# Sheet1.net
KiCad netlist of a schematic drawn in Altium Designer
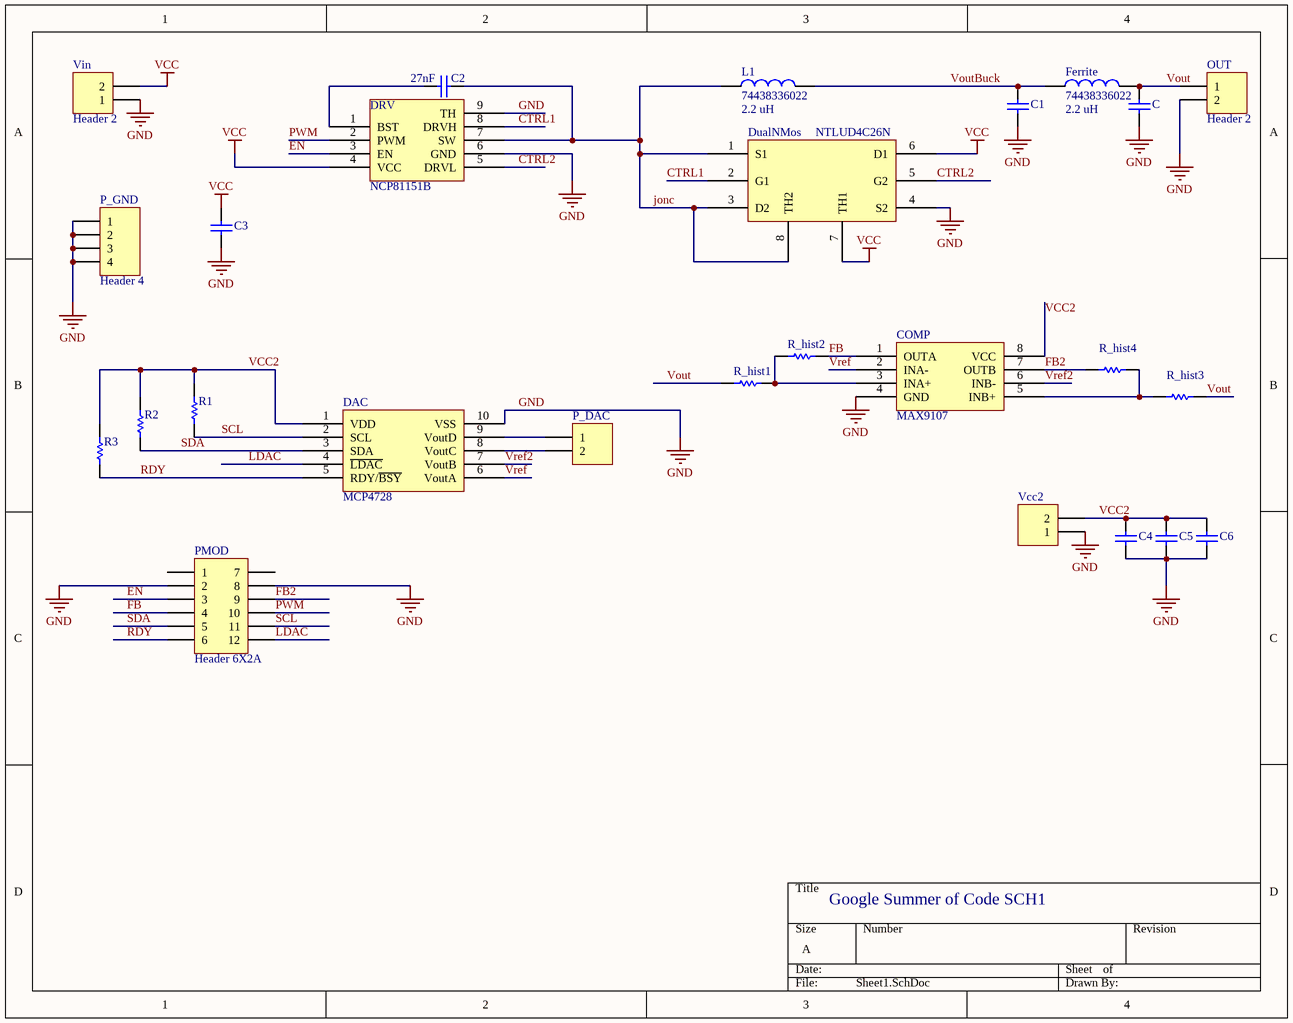
[diagram p0: Sheet1.SchDoc]

(export (version "E")
  (design (tool "Eeschema 10.0.6"))
  (components
    (comp (ref "C")
      (value "Cap")
      (footprint "Miscellaneous Devices:0603")
      (description "Capacitor")
      (fields (field (name "PUBLISHER") "Altium Limited"))
      (libsource (lib "Miscellaneous Devices") (part "Cap"))
    )
    (comp (ref "C1")
      (value "Cap")
      (footprint "Miscellaneous Devices:C1210_M")
      (description "Capacitor")
      (fields (field (name "PUBLISHER") "Altium Limited"))
      (libsource (lib "Miscellaneous Devices") (part "Cap"))
    )
    (comp (ref "C2")
      (value "27nF")
      (footprint "C0805")
      (description "Capacitor")
      (fields (field (name "Comment") "Cap") (field (name "PUBLISHER") "Altium Limited"))
      (libsource (lib "Miscellaneous Devices") (part "Cap"))
    )
    (comp (ref "C3")
      (value "Cap")
      (footprint "Miscellaneous Devices:C1210_M")
      (description "Capacitor")
      (fields (field (name "PUBLISHER") "Altium Limited"))
      (libsource (lib "Miscellaneous Devices") (part "Cap"))
    )
    (comp (ref "C4")
      (value "Cap")
      (footprint "Miscellaneous Devices:0402")
      (description "Capacitor")
      (fields (field (name "PUBLISHER") "Altium Limited"))
      (libsource (lib "Miscellaneous Devices") (part "Cap"))
    )
    (comp (ref "C5")
      (value "Cap")
      (footprint "Miscellaneous Devices:0402")
      (description "Capacitor")
      (fields (field (name "PUBLISHER") "Altium Limited"))
      (libsource (lib "Miscellaneous Devices") (part "Cap"))
    )
    (comp (ref "C6")
      (value "Cap")
      (footprint "Miscellaneous Devices:0402")
      (description "Capacitor")
      (fields (field (name "PUBLISHER") "Altium Limited"))
      (libsource (lib "Miscellaneous Devices") (part "Cap"))
    )
    (comp (ref "COMP") (value "MAX9107") (footprint "SOT23-8") (libsource (lib "BuckLib") (part "MAX9107")))
    (comp (ref "DAC")
      (value "MCP4728")
      (footprint "TSSOP50P500X110-10N")
      (libsource (lib "BuckLib") (part "MCP4728"))
    )
    (comp (ref "DRV")
      (value "NCP81151B")
      (footprint "QFN50P200X200X80_HS-9N")
      (libsource (lib "BuckLib") (part "NCP81151B"))
    )
    (comp (ref "DualNMos") (value "NTLUD4C26N") (libsource (lib "BuckLib") (part "NTLUD4C26N")))
    (comp (ref "Ferrite")
      (value "74438336022")
      (footprint "0402-A")
      (description "WE-MAPI SMD Shielded Power Inductor, size 3020, 2.2 uH")
      (fields (field (name "ALTIUM_VALUE") "2.2 uH") (field (name "PUBLISHER") "Wurth Elektronik"))
      (libsource (lib "ALTIUM-WE-MAPI-rev16b") (part "74438336022"))
    )
    (comp (ref "L1")
      (value "74438336022")
      (footprint "WE-MAPI_3020")
      (description "WE-MAPI SMD Shielded Power Inductor, size 3020, 2.2 uH")
      (fields (field (name "ALTIUM_VALUE") "2.2 uH") (field (name "PUBLISHER") "Wurth Elektronik"))
      (libsource (lib "ALTIUM-WE-MAPI-rev16b") (part "74438336022"))
    )
    (comp (ref "OUT")
      (value "Header 2")
      (footprint "HDR1X2")
      (description "Header, 2-Pin")
      (fields (field (name "PUBLISHER") "Altium Limited"))
      (libsource (lib "Miscellaneous Connectors") (part "Header 2"))
    )
    (comp (ref "PMOD")
      (value "Header 6X2A")
      (footprint "HDR2X6_CEN")
      (description "Header, 6-Pin, Dual row")
      (fields (field (name "PUBLISHER") "Altium Limited"))
      (libsource (lib "Miscellaneous Connectors") (part "Header 6X2A"))
    )
    (comp (ref "P_DAC")
      (value "Header 2")
      (footprint "HDR1X2")
      (description "Header, 2-Pin")
      (fields (field (name "PUBLISHER") "Altium Limited"))
      (libsource (lib "Miscellaneous Connectors") (part "Header 2"))
    )
    (comp (ref "P_GND")
      (value "Header 4")
      (footprint "HDR1X4")
      (description "Header, 4-Pin")
      (fields (field (name "PUBLISHER") "Altium Limited"))
      (libsource (lib "Miscellaneous Connectors") (part "Header 4"))
    )
    (comp (ref "R1")
      (value "Res1")
      (footprint "C0805")
      (description "Resistor")
      (fields (field (name "PUBLISHER") "Altium Limited"))
      (libsource (lib "Miscellaneous Devices") (part "Res1"))
    )
    (comp (ref "R2")
      (value "Res1")
      (footprint "C0805")
      (description "Resistor")
      (fields (field (name "PUBLISHER") "Altium Limited"))
      (libsource (lib "Miscellaneous Devices") (part "Res1"))
    )
    (comp (ref "R3")
      (value "Res1")
      (footprint "C0805")
      (description "Resistor")
      (fields (field (name "PUBLISHER") "Altium Limited"))
      (libsource (lib "Miscellaneous Devices") (part "Res1"))
    )
    (comp (ref "R_hist1")
      (value "Res1")
      (footprint "C0805")
      (description "Resistor")
      (fields (field (name "PUBLISHER") "Altium Limited"))
      (libsource (lib "Miscellaneous Devices") (part "Res1"))
    )
    (comp (ref "R_hist2")
      (value "Res1")
      (footprint "C0805")
      (description "Resistor")
      (fields (field (name "PUBLISHER") "Altium Limited"))
      (libsource (lib "Miscellaneous Devices") (part "Res1"))
    )
    (comp (ref "R_hist3")
      (value "Res1")
      (footprint "C0805")
      (description "Resistor")
      (fields (field (name "PUBLISHER") "Altium Limited"))
      (libsource (lib "Miscellaneous Devices") (part "Res1"))
    )
    (comp (ref "R_hist4")
      (value "Res1")
      (footprint "C0805")
      (description "Resistor")
      (fields (field (name "PUBLISHER") "Altium Limited"))
      (libsource (lib "Miscellaneous Devices") (part "Res1"))
    )
    (comp (ref "Vcc2")
      (value "Header 2")
      (footprint "HDR1X2")
      (description "Header, 2-Pin")
      (fields (field (name "PUBLISHER") "Altium Limited"))
      (libsource (lib "") (part "Header 2_1"))
    )
    (comp (ref "Vin")
      (value "Header 2")
      (footprint "HDR1X2")
      (description "Header, 2-Pin")
      (fields (field (name "PUBLISHER") "Altium Limited"))
      (libsource (lib "") (part "Header 2_1"))
    )
  )
  (nets
    (net (code "1") (name "/CTRL1") (class "Default")
      (node (ref "DRV") (pin "8") (pinfunction "DRVH_8") (pintype "passive"))
      (node (ref "DualNMos") (pin "2") (pinfunction "G1_2") (pintype "passive"))
    )
    (net (code "2") (name "/CTRL2") (class "Default")
      (node (ref "DRV") (pin "5") (pinfunction "DRVL_5") (pintype "passive"))
      (node (ref "DualNMos") (pin "5") (pinfunction "G2_5") (pintype "passive"))
    )
    (net (code "3") (name "/EN") (class "Default")
      (node (ref "DRV") (pin "3") (pinfunction "EN_3") (pintype "passive"))
      (node (ref "PMOD") (pin "3") (pinfunction "3_3") (pintype "passive"))
    )
    (net (code "4") (name "/FB") (class "Default")
      (node (ref "COMP") (pin "1") (pinfunction "OUTA_1") (pintype "passive"))
      (node (ref "PMOD") (pin "4") (pinfunction "4_4") (pintype "passive"))
      (node (ref "R_hist2") (pin "1") (pinfunction "1_1") (pintype "passive"))
    )
    (net (code "5") (name "/FB2") (class "Default")
      (node (ref "COMP") (pin "7") (pinfunction "OUTB_7") (pintype "passive"))
      (node (ref "PMOD") (pin "9") (pinfunction "9_9") (pintype "passive"))
      (node (ref "R_hist4") (pin "2") (pinfunction "2_2") (pintype "passive"))
    )
    (net (code "6") (name "/LDAC") (class "Default")
      (node (ref "DAC") (pin "4") (pinfunction "~{LDAC}_4") (pintype "passive"))
      (node (ref "PMOD") (pin "12") (pinfunction "12_12") (pintype "passive"))
    )
    (net (code "7") (name "/PWM") (class "Default")
      (node (ref "DRV") (pin "2") (pinfunction "PWM_2") (pintype "passive"))
      (node (ref "PMOD") (pin "10") (pinfunction "10_10") (pintype "passive"))
    )
    (net (code "8") (name "/RDY") (class "Default")
      (node (ref "DAC") (pin "5") (pinfunction "RDY/~{BSY}_5") (pintype "passive"))
      (node (ref "PMOD") (pin "6") (pinfunction "6_6") (pintype "passive"))
      (node (ref "R3") (pin "1") (pinfunction "1_1") (pintype "passive"))
    )
    (net (code "9") (name "/SCL") (class "Default")
      (node (ref "DAC") (pin "2") (pinfunction "SCL_2") (pintype "passive"))
      (node (ref "PMOD") (pin "11") (pinfunction "11_11") (pintype "passive"))
      (node (ref "R1") (pin "1") (pinfunction "1_1") (pintype "passive"))
    )
    (net (code "10") (name "/SDA") (class "Default")
      (node (ref "DAC") (pin "3") (pinfunction "SDA_3") (pintype "passive"))
      (node (ref "PMOD") (pin "5") (pinfunction "5_5") (pintype "passive"))
      (node (ref "R2") (pin "1") (pinfunction "1_1") (pintype "passive"))
    )
    (net (code "11") (name "/VCC2") (class "Default")
      (node (ref "C4") (pin "1") (pinfunction "1_1") (pintype "passive"))
      (node (ref "C5") (pin "1") (pinfunction "1_1") (pintype "passive"))
      (node (ref "C6") (pin "1") (pinfunction "1_1") (pintype "passive"))
      (node (ref "COMP") (pin "8") (pinfunction "VCC_8") (pintype "passive"))
      (node (ref "DAC") (pin "1") (pinfunction "VDD_1") (pintype "passive"))
      (node (ref "R1") (pin "2") (pinfunction "2_2") (pintype "passive"))
      (node (ref "R2") (pin "2") (pinfunction "2_2") (pintype "passive"))
      (node (ref "R3") (pin "2") (pinfunction "2_2") (pintype "passive"))
      (node (ref "Vcc2") (pin "2") (pinfunction "2_2") (pintype "passive"))
    )
    (net (code "12") (name "/Vout") (class "Default")
      (node (ref "C") (pin "2") (pinfunction "2_2") (pintype "passive"))
      (node (ref "Ferrite") (pin "2") (pinfunction "2_2") (pintype "passive"))
      (node (ref "OUT") (pin "1") (pinfunction "1_1") (pintype "passive"))
      (node (ref "R_hist1") (pin "2") (pinfunction "2_2") (pintype "passive"))
      (node (ref "R_hist3") (pin "1") (pinfunction "1_1") (pintype "passive"))
    )
    (net (code "13") (name "/VoutBuck") (class "Default")
      (node (ref "C1") (pin "2") (pinfunction "2_2") (pintype "passive"))
      (node (ref "Ferrite") (pin "1") (pinfunction "1_1") (pintype "passive"))
      (node (ref "L1") (pin "2") (pinfunction "2_2") (pintype "passive"))
    )
    (net (code "14") (name "/Vref") (class "Default")
      (node (ref "COMP") (pin "2") (pinfunction "INA-_2") (pintype "passive"))
      (node (ref "DAC") (pin "6") (pinfunction "VoutA_6") (pintype "passive"))
    )
    (net (code "15") (name "/Vref2") (class "Default")
      (node (ref "COMP") (pin "6") (pinfunction "INB-_6") (pintype "passive"))
      (node (ref "DAC") (pin "7") (pinfunction "VoutB_7") (pintype "passive"))
    )
    (net (code "16") (name "/jonc") (class "Default")
      (node (ref "C2") (pin "1") (pinfunction "1_1") (pintype "passive"))
      (node (ref "DRV") (pin "7") (pinfunction "SW_7") (pintype "passive"))
      (node (ref "DualNMos") (pin "1") (pinfunction "S1_1") (pintype "passive"))
      (node (ref "DualNMos") (pin "3") (pinfunction "D2_3") (pintype "passive"))
      (node (ref "DualNMos") (pin "8") (pinfunction "TH2_8") (pintype "passive"))
      (node (ref "L1") (pin "1") (pinfunction "1_1") (pintype "passive"))
    )
    (net (code "17") (name "GND") (class "Default")
      (node (ref "C") (pin "1") (pinfunction "1_1") (pintype "passive"))
      (node (ref "C1") (pin "1") (pinfunction "1_1") (pintype "passive"))
      (node (ref "C3") (pin "2") (pinfunction "2_2") (pintype "passive"))
      (node (ref "C4") (pin "2") (pinfunction "2_2") (pintype "passive"))
      (node (ref "C5") (pin "2") (pinfunction "2_2") (pintype "passive"))
      (node (ref "C6") (pin "2") (pinfunction "2_2") (pintype "passive"))
      (node (ref "COMP") (pin "4") (pinfunction "GND_4") (pintype "passive"))
      (node (ref "DAC") (pin "10") (pinfunction "VSS_10") (pintype "passive"))
      (node (ref "DRV") (pin "6") (pinfunction "GND_6") (pintype "passive"))
      (node (ref "DRV") (pin "9") (pinfunction "TH_9") (pintype "passive"))
      (node (ref "DualNMos") (pin "4") (pinfunction "S2_4") (pintype "passive"))
      (node (ref "OUT") (pin "2") (pinfunction "2_2") (pintype "passive"))
      (node (ref "PMOD") (pin "2") (pinfunction "2_2") (pintype "passive"))
      (node (ref "PMOD") (pin "8") (pinfunction "8_8") (pintype "passive"))
      (node (ref "P_GND") (pin "1") (pinfunction "1_1") (pintype "passive"))
      (node (ref "P_GND") (pin "2") (pinfunction "2_2") (pintype "passive"))
      (node (ref "P_GND") (pin "3") (pinfunction "3_3") (pintype "passive"))
      (node (ref "P_GND") (pin "4") (pinfunction "4_4") (pintype "passive"))
      (node (ref "Vcc2") (pin "1") (pinfunction "1_1") (pintype "passive"))
      (node (ref "Vin") (pin "1") (pinfunction "1_1") (pintype "passive"))
    )
    (net (code "18") (name "Net-(COMP-INA+)") (class "Default")
      (node (ref "COMP") (pin "3") (pinfunction "INA+_3") (pintype "passive"))
      (node (ref "R_hist1") (pin "1") (pinfunction "1_1") (pintype "passive"))
      (node (ref "R_hist2") (pin "2") (pinfunction "2_2") (pintype "passive"))
    )
    (net (code "19") (name "Net-(COMP-INB+)") (class "Default")
      (node (ref "COMP") (pin "5") (pinfunction "INB+_5") (pintype "passive"))
      (node (ref "R_hist3") (pin "2") (pinfunction "2_2") (pintype "passive"))
      (node (ref "R_hist4") (pin "1") (pinfunction "1_1") (pintype "passive"))
    )
    (net (code "20") (name "Net-(DAC-VoutC)") (class "Default")
      (node (ref "DAC") (pin "8") (pinfunction "VoutC_8") (pintype "passive"))
      (node (ref "P_DAC") (pin "2") (pinfunction "2_2") (pintype "passive"))
    )
    (net (code "21") (name "Net-(DAC-VoutD)") (class "Default")
      (node (ref "DAC") (pin "9") (pinfunction "VoutD_9") (pintype "passive"))
      (node (ref "P_DAC") (pin "1") (pinfunction "1_1") (pintype "passive"))
    )
    (net (code "22") (name "Net-(DRV-BST)") (class "Default")
      (node (ref "C2") (pin "2") (pinfunction "2_2") (pintype "passive"))
      (node (ref "DRV") (pin "1") (pinfunction "BST_1") (pintype "passive"))
    )
    (net (code "23") (name "VCC") (class "Default")
      (node (ref "C3") (pin "1") (pinfunction "1_1") (pintype "passive"))
      (node (ref "DRV") (pin "4") (pinfunction "VCC_4") (pintype "passive"))
      (node (ref "DualNMos") (pin "6") (pinfunction "D1_6") (pintype "passive"))
      (node (ref "DualNMos") (pin "7") (pinfunction "TH1_7") (pintype "passive"))
      (node (ref "Vin") (pin "2") (pinfunction "2_2") (pintype "passive"))
    )
    (net (code "24") (name "unconnected-(PMOD-Pad1)") (class "Default")
      (node (ref "PMOD") (pin "1") (pinfunction "1_1") (pintype "passive"))
    )
    (net (code "25") (name "unconnected-(PMOD-Pad7)") (class "Default")
      (node (ref "PMOD") (pin "7") (pinfunction "7_7") (pintype "passive"))
    )
  )
)
